# AudioMega_DIL-1206_TOP.net
KiCad netlist of a schematic drawn in EAGLE
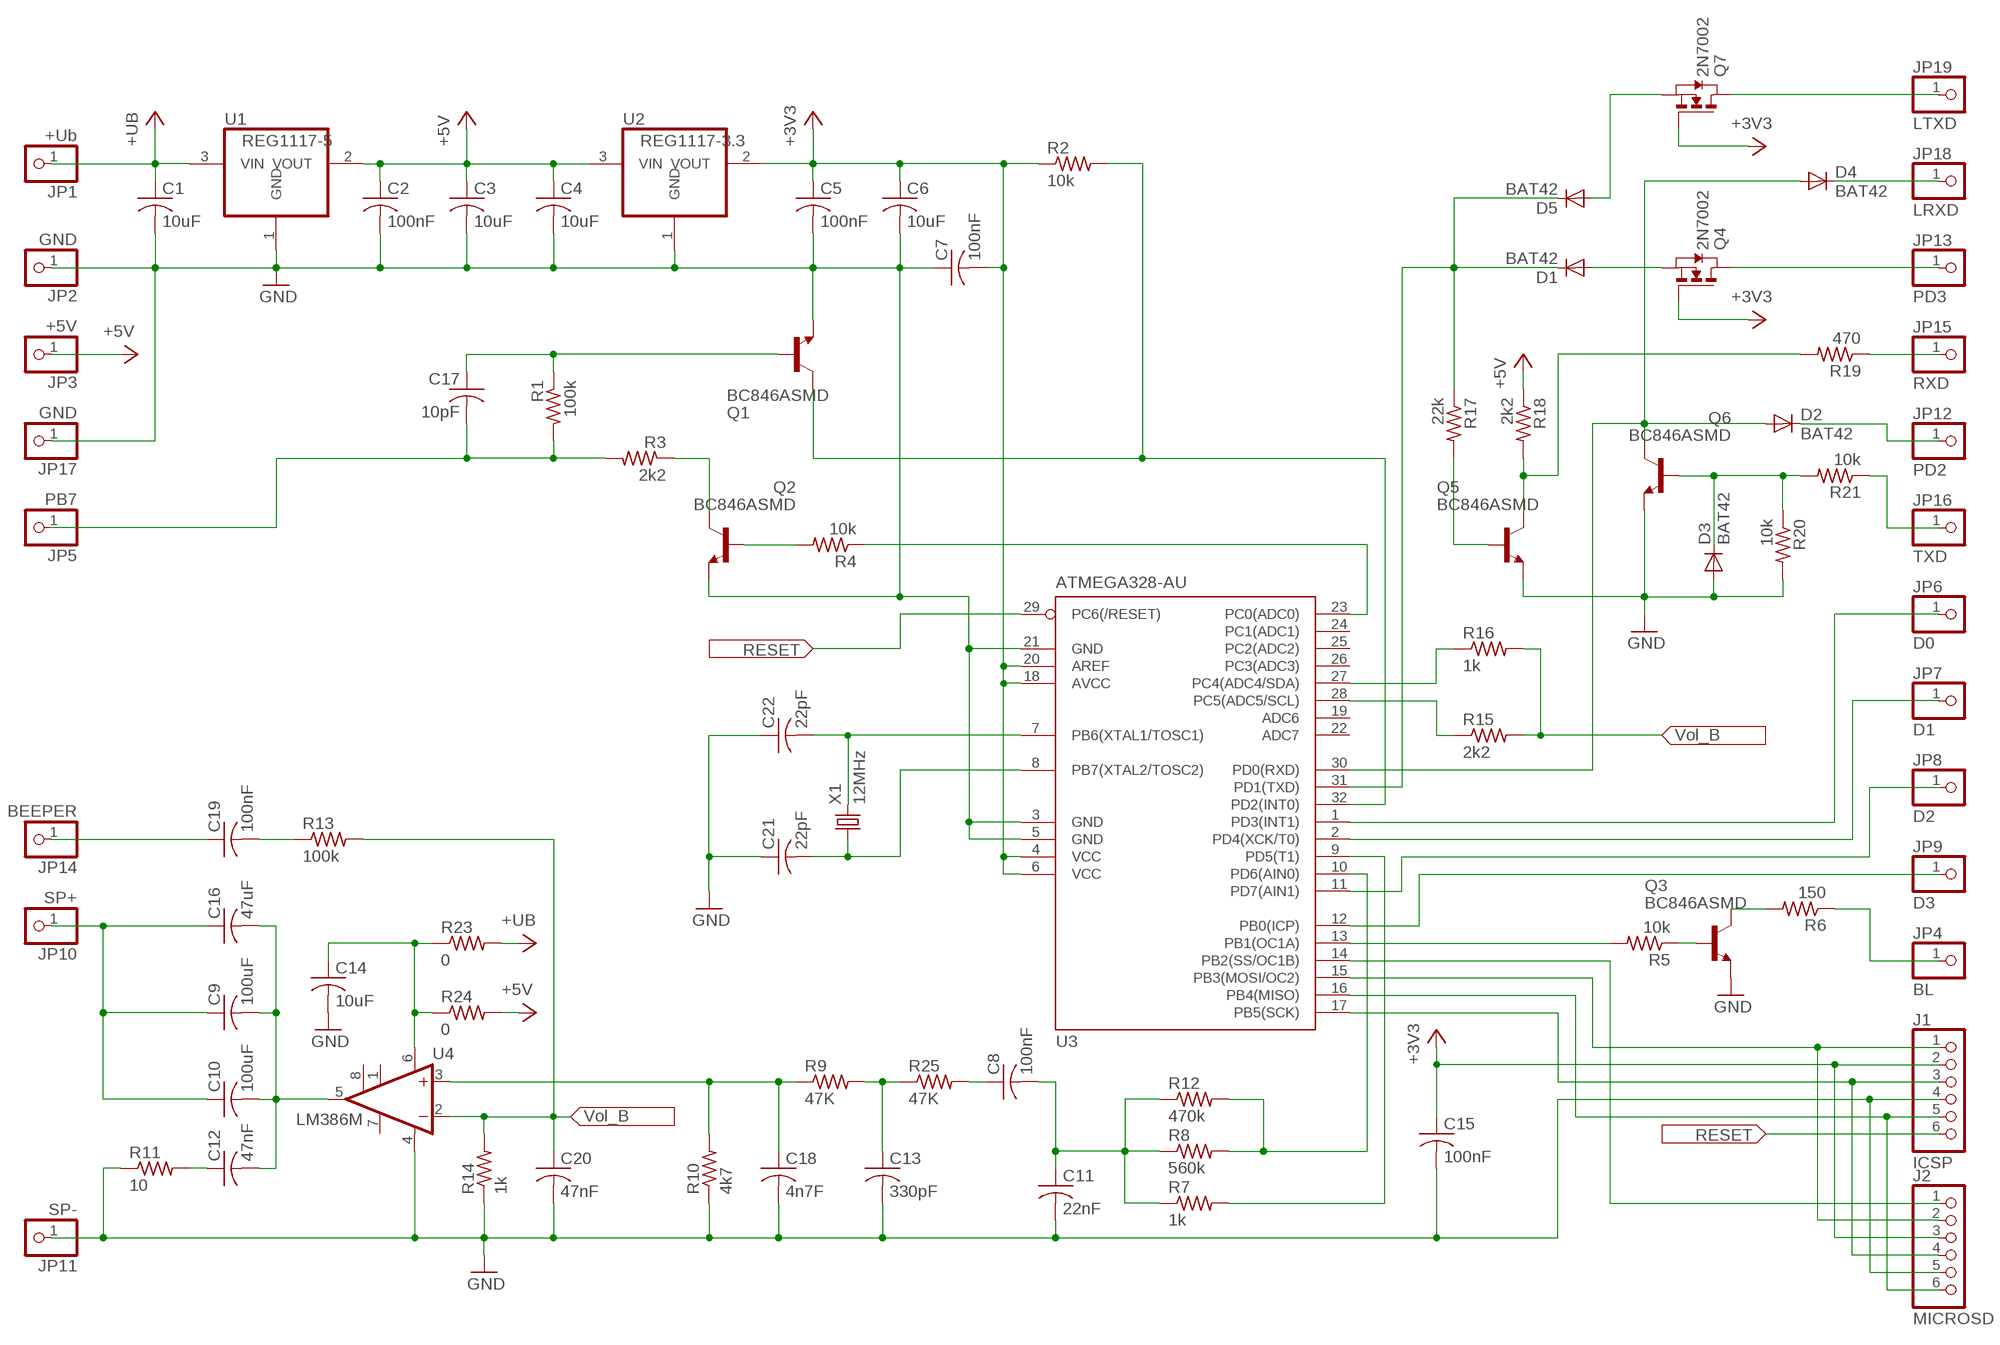
[diagram p0: schematic, sheet 1]

(export (version "E")
  (design (tool "Eeschema 10.0.6"))
  (components
    (comp (ref "C1")
      (value "10uF")
      (footprint "eagle-import:C1206")
      (libsource (lib "eagle-import") (part "C-USC1206"))
    )
    (comp (ref "C2")
      (value "100nF")
      (footprint "eagle-import:C1206")
      (libsource (lib "eagle-import") (part "C-USC1206"))
    )
    (comp (ref "C3")
      (value "10uF")
      (footprint "eagle-import:C1206")
      (libsource (lib "eagle-import") (part "C-USC1206"))
    )
    (comp (ref "C4")
      (value "10uF")
      (footprint "eagle-import:C1206")
      (libsource (lib "eagle-import") (part "C-USC1206"))
    )
    (comp (ref "C5")
      (value "100nF")
      (footprint "eagle-import:C1206")
      (libsource (lib "eagle-import") (part "C-USC1206"))
    )
    (comp (ref "C6")
      (value "10uF")
      (footprint "eagle-import:C1206")
      (libsource (lib "eagle-import") (part "C-USC1206"))
    )
    (comp (ref "C7")
      (value "100nF")
      (footprint "eagle-import:C1206")
      (libsource (lib "eagle-import") (part "C-USC1206"))
    )
    (comp (ref "C8")
      (value "100nF")
      (footprint "eagle-import:C1206")
      (libsource (lib "eagle-import") (part "C-USC1206"))
    )
    (comp (ref "C9")
      (value "100uF")
      (footprint "eagle-import:C1206")
      (libsource (lib "eagle-import") (part "C-USC1206"))
    )
    (comp (ref "C10")
      (value "100uF")
      (footprint "eagle-import:C1206")
      (libsource (lib "eagle-import") (part "C-USC1206"))
    )
    (comp (ref "C11")
      (value "22nF")
      (footprint "eagle-import:C1206")
      (libsource (lib "eagle-import") (part "C-USC1206"))
    )
    (comp (ref "C12")
      (value "47nF")
      (footprint "eagle-import:C1206")
      (libsource (lib "eagle-import") (part "C-USC1206"))
    )
    (comp (ref "C13")
      (value "330pF")
      (footprint "eagle-import:C1206")
      (libsource (lib "eagle-import") (part "C-USC1206"))
    )
    (comp (ref "C14")
      (value "10uF")
      (footprint "eagle-import:C1206")
      (libsource (lib "eagle-import") (part "C-USC1206"))
    )
    (comp (ref "C15")
      (value "100nF")
      (footprint "eagle-import:C1206")
      (libsource (lib "eagle-import") (part "C-USC1206"))
    )
    (comp (ref "C16")
      (value "47uF")
      (footprint "eagle-import:C1206")
      (libsource (lib "eagle-import") (part "C-USC1206"))
    )
    (comp (ref "C17")
      (value "10pF")
      (footprint "eagle-import:C1206")
      (libsource (lib "eagle-import") (part "C-USC1206"))
    )
    (comp (ref "C18")
      (value "4n7F")
      (footprint "eagle-import:C1206")
      (libsource (lib "eagle-import") (part "C-USC1206"))
    )
    (comp (ref "C19")
      (value "100nF")
      (footprint "eagle-import:C1206")
      (libsource (lib "eagle-import") (part "C-USC1206"))
    )
    (comp (ref "C20")
      (value "47nF")
      (footprint "eagle-import:C1206")
      (libsource (lib "eagle-import") (part "C-USC1206"))
    )
    (comp (ref "C21")
      (value "22pF")
      (footprint "eagle-import:C1206")
      (libsource (lib "eagle-import") (part "C-USC1206"))
    )
    (comp (ref "C22")
      (value "22pF")
      (footprint "eagle-import:C1206")
      (libsource (lib "eagle-import") (part "C-USC1206"))
    )
    (comp (ref "D1")
      (value "BAT42")
      (footprint "eagle-import:SOD123")
      (libsource (lib "eagle-import") (part "DIODE-SOD123"))
    )
    (comp (ref "D2")
      (value "BAT42")
      (footprint "eagle-import:SOD123")
      (libsource (lib "eagle-import") (part "DIODE-SOD123"))
    )
    (comp (ref "D3")
      (value "BAT42")
      (footprint "eagle-import:SOD123")
      (libsource (lib "eagle-import") (part "DIODE-SOD123"))
    )
    (comp (ref "D4")
      (value "BAT42")
      (footprint "eagle-import:SOD123")
      (libsource (lib "eagle-import") (part "DIODE-SOD123"))
    )
    (comp (ref "D5")
      (value "BAT42")
      (footprint "eagle-import:SOD123")
      (libsource (lib "eagle-import") (part "DIODE-SOD123"))
    )
    (comp (ref "J1")
      (value "ICSP")
      (footprint "eagle-import:1X06")
      (libsource (lib "eagle-import") (part "PINHD-1X6"))
    )
    (comp (ref "J2")
      (value "MICROSD")
      (footprint "eagle-import:1X06")
      (libsource (lib "eagle-import") (part "PINHD-1X6"))
    )
    (comp (ref "JP1")
      (value "+Ub")
      (footprint "eagle-import:1X01")
      (libsource (lib "eagle-import") (part "PINHD-1X1"))
    )
    (comp (ref "JP2")
      (value "GND")
      (footprint "eagle-import:1X01")
      (libsource (lib "eagle-import") (part "PINHD-1X1"))
    )
    (comp (ref "JP3")
      (value "+5V")
      (footprint "eagle-import:1X01")
      (libsource (lib "eagle-import") (part "PINHD-1X1"))
    )
    (comp (ref "JP4")
      (value "BL")
      (footprint "eagle-import:1X01")
      (libsource (lib "eagle-import") (part "PINHD-1X1"))
    )
    (comp (ref "JP5")
      (value "PB7")
      (footprint "eagle-import:1X01")
      (libsource (lib "eagle-import") (part "PINHD-1X1"))
    )
    (comp (ref "JP6")
      (value "D0")
      (footprint "eagle-import:1X01")
      (libsource (lib "eagle-import") (part "PINHD-1X1"))
    )
    (comp (ref "JP7")
      (value "D1")
      (footprint "eagle-import:1X01")
      (libsource (lib "eagle-import") (part "PINHD-1X1"))
    )
    (comp (ref "JP8")
      (value "D2")
      (footprint "eagle-import:1X01")
      (libsource (lib "eagle-import") (part "PINHD-1X1"))
    )
    (comp (ref "JP9")
      (value "D3")
      (footprint "eagle-import:1X01")
      (libsource (lib "eagle-import") (part "PINHD-1X1"))
    )
    (comp (ref "JP10")
      (value "SP+")
      (footprint "eagle-import:1X01")
      (libsource (lib "eagle-import") (part "PINHD-1X1"))
    )
    (comp (ref "JP11")
      (value "SP-")
      (footprint "eagle-import:1X01")
      (libsource (lib "eagle-import") (part "PINHD-1X1"))
    )
    (comp (ref "JP12")
      (value "PD2")
      (footprint "eagle-import:1X01")
      (libsource (lib "eagle-import") (part "PINHD-1X1"))
    )
    (comp (ref "JP13")
      (value "PD3")
      (footprint "eagle-import:1X01")
      (libsource (lib "eagle-import") (part "PINHD-1X1"))
    )
    (comp (ref "JP14")
      (value "BEEPER")
      (footprint "eagle-import:1X01")
      (libsource (lib "eagle-import") (part "PINHD-1X1"))
    )
    (comp (ref "JP15")
      (value "RXD")
      (footprint "eagle-import:1X01")
      (libsource (lib "eagle-import") (part "PINHD-1X1"))
    )
    (comp (ref "JP16")
      (value "TXD")
      (footprint "eagle-import:1X01")
      (libsource (lib "eagle-import") (part "PINHD-1X1"))
    )
    (comp (ref "JP17")
      (value "GND")
      (footprint "eagle-import:1X01")
      (libsource (lib "eagle-import") (part "PINHD-1X1"))
    )
    (comp (ref "JP18")
      (value "LRXD")
      (footprint "eagle-import:1X01")
      (libsource (lib "eagle-import") (part "PINHD-1X1"))
    )
    (comp (ref "JP19")
      (value "LTXD")
      (footprint "eagle-import:1X01")
      (libsource (lib "eagle-import") (part "PINHD-1X1"))
    )
    (comp (ref "Q1")
      (value "BC846ASMD")
      (footprint "eagle-import:SOT23")
      (libsource (lib "eagle-import") (part "BC846SMDA"))
    )
    (comp (ref "Q2")
      (value "BC846ASMD")
      (footprint "eagle-import:SOT23")
      (libsource (lib "eagle-import") (part "BC846SMDA"))
    )
    (comp (ref "Q3")
      (value "BC846ASMD")
      (footprint "eagle-import:SOT23")
      (libsource (lib "eagle-import") (part "BC846SMDA"))
    )
    (comp (ref "Q4")
      (value "2N7002")
      (footprint "eagle-import:SOT-23")
      (libsource (lib "eagle-import") (part "NMOSSOT23"))
    )
    (comp (ref "Q5")
      (value "BC846ASMD")
      (footprint "eagle-import:SOT23")
      (libsource (lib "eagle-import") (part "BC846SMDA"))
    )
    (comp (ref "Q6")
      (value "BC846ASMD")
      (footprint "eagle-import:SOT23")
      (libsource (lib "eagle-import") (part "BC846SMDA"))
    )
    (comp (ref "Q7")
      (value "2N7002")
      (footprint "eagle-import:SOT-23")
      (fields (field (name "OC_FARNELL") "unknown") (field (name "OC_NEWARK") "unknown"))
      (libsource (lib "eagle-import") (part "NMOSSOT23"))
    )
    (comp (ref "R1")
      (value "100k")
      (footprint "eagle-import:R1206")
      (libsource (lib "eagle-import") (part "resistor_R-US_R1206"))
    )
    (comp (ref "R2")
      (value "10k")
      (footprint "eagle-import:R1206")
      (libsource (lib "eagle-import") (part "resistor_R-US_R1206"))
    )
    (comp (ref "R3")
      (value "2k2")
      (footprint "eagle-import:R1206")
      (libsource (lib "eagle-import") (part "resistor_R-US_R1206"))
    )
    (comp (ref "R4")
      (value "10k")
      (footprint "eagle-import:R1206")
      (libsource (lib "eagle-import") (part "resistor_R-US_R1206"))
    )
    (comp (ref "R5")
      (value "10k")
      (footprint "eagle-import:R1206")
      (libsource (lib "eagle-import") (part "resistor_R-US_R1206"))
    )
    (comp (ref "R6")
      (value "150")
      (footprint "eagle-import:R1206")
      (libsource (lib "eagle-import") (part "resistor_R-US_R1206"))
    )
    (comp (ref "R7")
      (value "1k")
      (footprint "eagle-import:R1206")
      (libsource (lib "eagle-import") (part "resistor_R-US_R1206"))
    )
    (comp (ref "R8")
      (value "560k")
      (footprint "eagle-import:R1206")
      (libsource (lib "eagle-import") (part "resistor_R-US_R1206"))
    )
    (comp (ref "R9")
      (value "47K")
      (footprint "eagle-import:R1206")
      (libsource (lib "eagle-import") (part "resistor_R-US_R1206"))
    )
    (comp (ref "R10")
      (value "4k7")
      (footprint "eagle-import:R1206")
      (libsource (lib "eagle-import") (part "resistor_R-US_R1206"))
    )
    (comp (ref "R11")
      (value "10")
      (footprint "eagle-import:R1206")
      (libsource (lib "eagle-import") (part "resistor_R-US_R1206"))
    )
    (comp (ref "R12")
      (value "470k")
      (footprint "eagle-import:R1206")
      (libsource (lib "eagle-import") (part "resistor_R-US_R1206"))
    )
    (comp (ref "R13")
      (value "100k")
      (footprint "eagle-import:R1206")
      (libsource (lib "eagle-import") (part "resistor_R-US_R1206"))
    )
    (comp (ref "R14")
      (value "1k")
      (footprint "eagle-import:R1206")
      (libsource (lib "eagle-import") (part "resistor_R-US_R1206"))
    )
    (comp (ref "R15")
      (value "2k2")
      (footprint "eagle-import:R1206")
      (libsource (lib "eagle-import") (part "resistor_R-US_R1206"))
    )
    (comp (ref "R16")
      (value "1k")
      (footprint "eagle-import:R1206")
      (libsource (lib "eagle-import") (part "resistor_R-US_R1206"))
    )
    (comp (ref "R17")
      (value "22k")
      (footprint "eagle-import:R1206")
      (libsource (lib "eagle-import") (part "resistor_R-US_R1206"))
    )
    (comp (ref "R18")
      (value "2k2")
      (footprint "eagle-import:R1206")
      (libsource (lib "eagle-import") (part "resistor_R-US_R1206"))
    )
    (comp (ref "R19")
      (value "470")
      (footprint "eagle-import:R1206")
      (libsource (lib "eagle-import") (part "resistor_R-US_R1206"))
    )
    (comp (ref "R20")
      (value "10k")
      (footprint "eagle-import:R1206")
      (libsource (lib "eagle-import") (part "resistor_R-US_R1206"))
    )
    (comp (ref "R21")
      (value "10k")
      (footprint "eagle-import:R1206")
      (libsource (lib "eagle-import") (part "resistor_R-US_R1206"))
    )
    (comp (ref "R23")
      (value "0")
      (footprint "eagle-import:R1206")
      (libsource (lib "eagle-import") (part "R-US_R1206"))
    )
    (comp (ref "R24")
      (value "0")
      (footprint "eagle-import:R1206")
      (libsource (lib "eagle-import") (part "R-US_R1206"))
    )
    (comp (ref "R25")
      (value "47K")
      (footprint "eagle-import:R1206")
      (libsource (lib "eagle-import") (part "resistor_R-US_R1206"))
    )
    (comp (ref "U1")
      (value "REG1117-5")
      (footprint "eagle-import:SOT223")
      (fields (field (name "MPN") "REG1117"))
      (libsource (lib "eagle-import") (part "REG1117"))
    )
    (comp (ref "U2")
      (value "REG1117-3.3")
      (footprint "eagle-import:SOT223")
      (fields (field (name "MPN") "REG1117"))
      (libsource (lib "eagle-import") (part "REG1117"))
    )
    (comp (ref "U3")
      (value "ATMEGA328-AU")
      (footprint "eagle-import:TQFP32-08")
      (fields (field (name "MPN") "ATMEGA8-16AU"))
      (libsource (lib "eagle-import") (part "MEGA8-AI"))
    )
    (comp (ref "U4")
      (value "LM386M")
      (footprint "eagle-import:SO08")
      (libsource (lib "eagle-import") (part "LM386?-M1"))
    )
    (comp (ref "X1")
      (value "12MHz")
      (footprint "eagle-import:HC49US")
      (libsource (lib "eagle-import") (part "CSM-3XHC49/US"))
    )
  )
  (nets
    (net (code "1") (name "+3V3") (class "Default")
      (node (ref "C15") (pin "1") (pinfunction "1_1") (pintype "passive"))
      (node (ref "C5") (pin "1") (pinfunction "1_1") (pintype "passive"))
      (node (ref "C6") (pin "1") (pinfunction "1_1") (pintype "passive"))
      (node (ref "C7") (pin "2") (pinfunction "2_2") (pintype "passive"))
      (node (ref "J1") (pin "2") (pinfunction "2_2") (pintype "passive"))
      (node (ref "J2") (pin "3") (pinfunction "3_3") (pintype "passive"))
      (node (ref "Q4") (pin "3") (pinfunction "G_3") (pintype "passive"))
      (node (ref "Q7") (pin "3") (pinfunction "G_3") (pintype "passive"))
      (node (ref "R2") (pin "1") (pinfunction "1_1") (pintype "passive"))
      (node (ref "U2") (pin "2") (pinfunction "VOUT_2") (pintype "output"))
      (node (ref "U3") (pin "18") (pinfunction "AVCC_18") (pintype "power_in"))
      (node (ref "U3") (pin "20") (pinfunction "AREF_20") (pintype "passive"))
      (node (ref "U3") (pin "4") (pinfunction "VCC_4") (pintype "power_in"))
      (node (ref "U3") (pin "6") (pinfunction "VCC_6") (pintype "power_in"))
    )
    (net (code "2") (name "+5V") (class "Default")
      (node (ref "C2") (pin "1") (pinfunction "1_1") (pintype "passive"))
      (node (ref "C3") (pin "1") (pinfunction "1_1") (pintype "passive"))
      (node (ref "C4") (pin "1") (pinfunction "1_1") (pintype "passive"))
      (node (ref "JP3") (pin "1") (pinfunction "1_1") (pintype "passive"))
      (node (ref "R18") (pin "1") (pinfunction "1_1") (pintype "passive"))
      (node (ref "R24") (pin "2") (pinfunction "2_2") (pintype "passive"))
      (node (ref "U1") (pin "2") (pinfunction "VOUT_2") (pintype "output"))
      (node (ref "U2") (pin "3") (pinfunction "VIN_3") (pintype "input"))
    )
    (net (code "3") (name "+UB") (class "Default")
      (node (ref "C1") (pin "1") (pinfunction "1_1") (pintype "passive"))
      (node (ref "JP1") (pin "1") (pinfunction "1_1") (pintype "passive"))
      (node (ref "R23") (pin "2") (pinfunction "2_2") (pintype "passive"))
      (node (ref "U1") (pin "3") (pinfunction "VIN_3") (pintype "input"))
    )
    (net (code "4") (name "/RESET") (class "Default")
      (node (ref "J1") (pin "6") (pinfunction "6_6") (pintype "passive"))
      (node (ref "U3") (pin "29") (pinfunction "PC6(/RESET)_29") (pintype "bidirectional"))
    )
    (net (code "5") (name "/VOL_B") (class "Default")
      (node (ref "C20") (pin "1") (pinfunction "1_1") (pintype "passive"))
      (node (ref "R13") (pin "2") (pinfunction "2_2") (pintype "passive"))
      (node (ref "R14") (pin "2") (pinfunction "2_2") (pintype "passive"))
      (node (ref "R15") (pin "2") (pinfunction "2_2") (pintype "passive"))
      (node (ref "R16") (pin "2") (pinfunction "2_2") (pintype "passive"))
      (node (ref "U4") (pin "2") (pinfunction "-IN_2") (pintype "input"))
    )
    (net (code "6") (name "GND") (class "Default")
      (node (ref "C1") (pin "2") (pinfunction "2_2") (pintype "passive"))
      (node (ref "C11") (pin "2") (pinfunction "2_2") (pintype "passive"))
      (node (ref "C13") (pin "2") (pinfunction "2_2") (pintype "passive"))
      (node (ref "C14") (pin "2") (pinfunction "2_2") (pintype "passive"))
      (node (ref "C15") (pin "2") (pinfunction "2_2") (pintype "passive"))
      (node (ref "C18") (pin "2") (pinfunction "2_2") (pintype "passive"))
      (node (ref "C2") (pin "2") (pinfunction "2_2") (pintype "passive"))
      (node (ref "C20") (pin "2") (pinfunction "2_2") (pintype "passive"))
      (node (ref "C21") (pin "1") (pinfunction "1_1") (pintype "passive"))
      (node (ref "C22") (pin "1") (pinfunction "1_1") (pintype "passive"))
      (node (ref "C3") (pin "2") (pinfunction "2_2") (pintype "passive"))
      (node (ref "C4") (pin "2") (pinfunction "2_2") (pintype "passive"))
      (node (ref "C5") (pin "2") (pinfunction "2_2") (pintype "passive"))
      (node (ref "C6") (pin "2") (pinfunction "2_2") (pintype "passive"))
      (node (ref "C7") (pin "1") (pinfunction "1_1") (pintype "passive"))
      (node (ref "D3") (pin "A") (pinfunction "A_A") (pintype "passive"))
      (node (ref "J1") (pin "4") (pinfunction "4_4") (pintype "passive"))
      (node (ref "J2") (pin "5") (pinfunction "5_5") (pintype "passive"))
      (node (ref "JP11") (pin "1") (pinfunction "1_1") (pintype "passive"))
      (node (ref "JP17") (pin "1") (pinfunction "1_1") (pintype "passive"))
      (node (ref "JP2") (pin "1") (pinfunction "1_1") (pintype "passive"))
      (node (ref "Q1") (pin "2") (pinfunction "E_2") (pintype "passive"))
      (node (ref "Q2") (pin "2") (pinfunction "E_2") (pintype "passive"))
      (node (ref "Q3") (pin "2") (pinfunction "E_2") (pintype "passive"))
      (node (ref "Q5") (pin "2") (pinfunction "E_2") (pintype "passive"))
      (node (ref "Q6") (pin "2") (pinfunction "E_2") (pintype "passive"))
      (node (ref "R10") (pin "1") (pinfunction "1_1") (pintype "passive"))
      (node (ref "R11") (pin "1") (pinfunction "1_1") (pintype "passive"))
      (node (ref "R14") (pin "1") (pinfunction "1_1") (pintype "passive"))
      (node (ref "R20") (pin "2") (pinfunction "2_2") (pintype "passive"))
      (node (ref "U1") (pin "1") (pinfunction "GND_1") (pintype "power_in"))
      (node (ref "U2") (pin "1") (pinfunction "GND_1") (pintype "power_in"))
      (node (ref "U3") (pin "21") (pinfunction "GND_21") (pintype "power_in"))
      (node (ref "U3") (pin "3") (pinfunction "GND_3") (pintype "power_in"))
      (node (ref "U3") (pin "5") (pinfunction "GND_5") (pintype "power_in"))
      (node (ref "U4") (pin "4") (pinfunction "GND_4") (pintype "power_in"))
    )
    (net (code "7") (name "Net-(C8-Pad1)") (class "Default")
      (node (ref "C8") (pin "1") (pinfunction "1_1") (pintype "passive"))
      (node (ref "R25") (pin "2") (pinfunction "2_2") (pintype "passive"))
    )
    (net (code "8") (name "Net-(C10-Pad1)") (class "Default")
      (node (ref "C10") (pin "1") (pinfunction "1_1") (pintype "passive"))
      (node (ref "C16") (pin "1") (pinfunction "1_1") (pintype "passive"))
      (node (ref "C9") (pin "1") (pinfunction "1_1") (pintype "passive"))
      (node (ref "JP10") (pin "1") (pinfunction "1_1") (pintype "passive"))
    )
    (net (code "9") (name "Net-(C11-Pad1)") (class "Default")
      (node (ref "C11") (pin "1") (pinfunction "1_1") (pintype "passive"))
      (node (ref "C8") (pin "2") (pinfunction "2_2") (pintype "passive"))
      (node (ref "R12") (pin "1") (pinfunction "1_1") (pintype "passive"))
      (node (ref "R7") (pin "1") (pinfunction "1_1") (pintype "passive"))
      (node (ref "R8") (pin "1") (pinfunction "1_1") (pintype "passive"))
    )
    (net (code "10") (name "Net-(C12-Pad1)") (class "Default")
      (node (ref "C12") (pin "1") (pinfunction "1_1") (pintype "passive"))
      (node (ref "R11") (pin "2") (pinfunction "2_2") (pintype "passive"))
    )
    (net (code "11") (name "Net-(C13-Pad1)") (class "Default")
      (node (ref "C13") (pin "1") (pinfunction "1_1") (pintype "passive"))
      (node (ref "R25") (pin "1") (pinfunction "1_1") (pintype "passive"))
      (node (ref "R9") (pin "2") (pinfunction "2_2") (pintype "passive"))
    )
    (net (code "12") (name "Net-(C17-Pad2)") (class "Default")
      (node (ref "C17") (pin "2") (pinfunction "2_2") (pintype "passive"))
      (node (ref "JP5") (pin "1") (pinfunction "1_1") (pintype "passive"))
      (node (ref "R1") (pin "2") (pinfunction "2_2") (pintype "passive"))
      (node (ref "R3") (pin "2") (pinfunction "2_2") (pintype "passive"))
    )
    (net (code "13") (name "Net-(C19-Pad1)") (class "Default")
      (node (ref "C19") (pin "1") (pinfunction "1_1") (pintype "passive"))
      (node (ref "JP14") (pin "1") (pinfunction "1_1") (pintype "passive"))
    )
    (net (code "14") (name "Net-(C19-Pad2)") (class "Default")
      (node (ref "C19") (pin "2") (pinfunction "2_2") (pintype "passive"))
      (node (ref "R13") (pin "1") (pinfunction "1_1") (pintype "passive"))
    )
    (net (code "15") (name "Net-(D2-PadC)") (class "Default")
      (node (ref "D2") (pin "C") (pinfunction "C_C") (pintype "passive"))
      (node (ref "JP12") (pin "1") (pinfunction "1_1") (pintype "passive"))
    )
    (net (code "16") (name "Net-(D4-PadC)") (class "Default")
      (node (ref "D4") (pin "C") (pinfunction "C_C") (pintype "passive"))
      (node (ref "JP18") (pin "1") (pinfunction "1_1") (pintype "passive"))
    )
    (net (code "17") (name "Net-(JP4-Pad1)") (class "Default")
      (node (ref "JP4") (pin "1") (pinfunction "1_1") (pintype "passive"))
      (node (ref "R6") (pin "1") (pinfunction "1_1") (pintype "passive"))
    )
    (net (code "18") (name "Net-(JP15-Pad1)") (class "Default")
      (node (ref "JP15") (pin "1") (pinfunction "1_1") (pintype "passive"))
      (node (ref "R19") (pin "1") (pinfunction "1_1") (pintype "passive"))
    )
    (net (code "19") (name "Net-(JP16-Pad1)") (class "Default")
      (node (ref "JP16") (pin "1") (pinfunction "1_1") (pintype "passive"))
      (node (ref "R21") (pin "1") (pinfunction "1_1") (pintype "passive"))
    )
    (net (code "20") (name "Net-(Q1-B)") (class "Default")
      (node (ref "C17") (pin "1") (pinfunction "1_1") (pintype "passive"))
      (node (ref "Q1") (pin "1") (pinfunction "B_1") (pintype "passive"))
      (node (ref "R1") (pin "1") (pinfunction "1_1") (pintype "passive"))
    )
    (net (code "21") (name "Net-(Q1-C)") (class "Default")
      (node (ref "Q1") (pin "3") (pinfunction "C_3") (pintype "passive"))
      (node (ref "R2") (pin "2") (pinfunction "2_2") (pintype "passive"))
      (node (ref "U3") (pin "32") (pinfunction "PD2(INT0)_32") (pintype "bidirectional"))
    )
    (net (code "22") (name "Net-(Q2-B)") (class "Default")
      (node (ref "Q2") (pin "1") (pinfunction "B_1") (pintype "passive"))
      (node (ref "R4") (pin "2") (pinfunction "2_2") (pintype "passive"))
    )
    (net (code "23") (name "Net-(Q2-C)") (class "Default")
      (node (ref "Q2") (pin "3") (pinfunction "C_3") (pintype "passive"))
      (node (ref "R3") (pin "1") (pinfunction "1_1") (pintype "passive"))
    )
    (net (code "24") (name "Net-(Q3-B)") (class "Default")
      (node (ref "Q3") (pin "1") (pinfunction "B_1") (pintype "passive"))
      (node (ref "R5") (pin "1") (pinfunction "1_1") (pintype "passive"))
    )
    (net (code "25") (name "Net-(Q3-C)") (class "Default")
      (node (ref "Q3") (pin "3") (pinfunction "C_3") (pintype "passive"))
      (node (ref "R6") (pin "2") (pinfunction "2_2") (pintype "passive"))
    )
    (net (code "26") (name "Net-(Q4-D)") (class "Default")
      (node (ref "JP13") (pin "1") (pinfunction "1_1") (pintype "passive"))
      (node (ref "Q4") (pin "1") (pinfunction "D_1") (pintype "passive"))
    )
    (net (code "27") (name "Net-(Q4-S)") (class "Default")
      (node (ref "D1") (pin "A") (pinfunction "A_A") (pintype "passive"))
      (node (ref "Q4") (pin "2") (pinfunction "S_2") (pintype "passive"))
    )
    (net (code "28") (name "Net-(Q5-B)") (class "Default")
      (node (ref "Q5") (pin "1") (pinfunction "B_1") (pintype "passive"))
      (node (ref "R17") (pin "2") (pinfunction "2_2") (pintype "passive"))
    )
    (net (code "29") (name "Net-(Q5-C)") (class "Default")
      (node (ref "Q5") (pin "3") (pinfunction "C_3") (pintype "passive"))
      (node (ref "R18") (pin "2") (pinfunction "2_2") (pintype "passive"))
      (node (ref "R19") (pin "2") (pinfunction "2_2") (pintype "passive"))
    )
    (net (code "30") (name "Net-(Q6-B)") (class "Default")
      (node (ref "D3") (pin "C") (pinfunction "C_C") (pintype "passive"))
      (node (ref "Q6") (pin "1") (pinfunction "B_1") (pintype "passive"))
      (node (ref "R20") (pin "1") (pinfunction "1_1") (pintype "passive"))
      (node (ref "R21") (pin "2") (pinfunction "2_2") (pintype "passive"))
    )
    (net (code "31") (name "Net-(Q6-C)") (class "Default")
      (node (ref "D2") (pin "A") (pinfunction "A_A") (pintype "passive"))
      (node (ref "D4") (pin "A") (pinfunction "A_A") (pintype "passive"))
      (node (ref "Q6") (pin "3") (pinfunction "C_3") (pintype "passive"))
      (node (ref "U3") (pin "30") (pinfunction "PD0(RXD)_30") (pintype "bidirectional"))
    )
    (net (code "32") (name "Net-(Q7-D)") (class "Default")
      (node (ref "JP19") (pin "1") (pinfunction "1_1") (pintype "passive"))
      (node (ref "Q7") (pin "1") (pinfunction "D_1") (pintype "passive"))
    )
    (net (code "33") (name "Net-(Q7-S)") (class "Default")
      (node (ref "D5") (pin "A") (pinfunction "A_A") (pintype "passive"))
      (node (ref "Q7") (pin "2") (pinfunction "S_2") (pintype "passive"))
    )
    (net (code "34") (name "Net-(U3-PB0(ICP))") (class "Default")
      (node (ref "JP9") (pin "1") (pinfunction "1_1") (pintype "passive"))
      (node (ref "U3") (pin "12") (pinfunction "PB0(ICP)_12") (pintype "bidirectional"))
    )
    (net (code "35") (name "Net-(U3-PB1(OC1A))") (class "Default")
      (node (ref "R5") (pin "2") (pinfunction "2_2") (pintype "passive"))
      (node (ref "U3") (pin "13") (pinfunction "PB1(OC1A)_13") (pintype "bidirectional"))
    )
    (net (code "36") (name "Net-(U3-PB2(SS{slash}OC1B))") (class "Default")
      (node (ref "J2") (pin "1") (pinfunction "1_1") (pintype "passive"))
      (node (ref "U3") (pin "14") (pinfunction "PB2(SS/OC1B)_14") (pintype "bidirectional"))
    )
    (net (code "37") (name "Net-(U3-PB3(MOSI{slash}OC2))") (class "Default")
      (node (ref "J1") (pin "1") (pinfunction "1_1") (pintype "passive"))
      (node (ref "J2") (pin "2") (pinfunction "2_2") (pintype "passive"))
      (node (ref "U3") (pin "15") (pinfunction "PB3(MOSI/OC2)_15") (pintype "bidirectional"))
    )
    (net (code "38") (name "Net-(U3-PB4(MISO))") (class "Default")
      (node (ref "J1") (pin "5") (pinfunction "5_5") (pintype "passive"))
      (node (ref "J2") (pin "6") (pinfunction "6_6") (pintype "passive"))
      (node (ref "U3") (pin "16") (pinfunction "PB4(MISO)_16") (pintype "bidirectional"))
    )
    (net (code "39") (name "Net-(U3-PB5(SCK))") (class "Default")
      (node (ref "J1") (pin "3") (pinfunction "3_3") (pintype "passive"))
      (node (ref "J2") (pin "4") (pinfunction "4_4") (pintype "passive"))
      (node (ref "U3") (pin "17") (pinfunction "PB5(SCK)_17") (pintype "bidirectional"))
    )
    (net (code "40") (name "Net-(U3-PB6(XTAL1{slash}TOSC1))") (class "Default")
      (node (ref "C22") (pin "2") (pinfunction "2_2") (pintype "passive"))
      (node (ref "U3") (pin "7") (pinfunction "PB6(XTAL1/TOSC1)_7") (pintype "bidirectional"))
      (node (ref "X1") (pin "2") (pinfunction "2_2") (pintype "passive"))
    )
    (net (code "41") (name "Net-(U3-PB7(XTAL2{slash}TOSC2))") (class "Default")
      (node (ref "C21") (pin "2") (pinfunction "2_2") (pintype "passive"))
      (node (ref "U3") (pin "8") (pinfunction "PB7(XTAL2/TOSC2)_8") (pintype "bidirectional"))
      (node (ref "X1") (pin "1") (pinfunction "1_1") (pintype "passive"))
    )
    (net (code "42") (name "Net-(U3-PC0(ADC0))") (class "Default")
      (node (ref "R4") (pin "1") (pinfunction "1_1") (pintype "passive"))
      (node (ref "U3") (pin "23") (pinfunction "PC0(ADC0)_23") (pintype "bidirectional"))
    )
    (net (code "43") (name "Net-(U3-PC4(ADC4{slash}SDA))") (class "Default")
      (node (ref "R16") (pin "1") (pinfunction "1_1") (pintype "passive"))
      (node (ref "U3") (pin "27") (pinfunction "PC4(ADC4/SDA)_27") (pintype "bidirectional"))
    )
    (net (code "44") (name "Net-(U3-PC5(ADC5{slash}SCL))") (class "Default")
      (node (ref "R15") (pin "1") (pinfunction "1_1") (pintype "passive"))
      (node (ref "U3") (pin "28") (pinfunction "PC5(ADC5/SCL)_28") (pintype "bidirectional"))
    )
    (net (code "45") (name "Net-(U3-PD1(TXD))") (class "Default")
      (node (ref "D1") (pin "C") (pinfunction "C_C") (pintype "passive"))
      (node (ref "D5") (pin "C") (pinfunction "C_C") (pintype "passive"))
      (node (ref "R17") (pin "1") (pinfunction "1_1") (pintype "passive"))
      (node (ref "U3") (pin "31") (pinfunction "PD1(TXD)_31") (pintype "bidirectional"))
    )
    (net (code "46") (name "Net-(U3-PD3(INT1))") (class "Default")
      (node (ref "JP6") (pin "1") (pinfunction "1_1") (pintype "passive"))
      (node (ref "U3") (pin "1") (pinfunction "PD3(INT1)_1") (pintype "bidirectional"))
    )
    (net (code "47") (name "Net-(U3-PD4(XCK{slash}T0))") (class "Default")
      (node (ref "JP7") (pin "1") (pinfunction "1_1") (pintype "passive"))
      (node (ref "U3") (pin "2") (pinfunction "PD4(XCK/T0)_2") (pintype "bidirectional"))
    )
    (net (code "48") (name "Net-(U3-PD5(T1))") (class "Default")
      (node (ref "R7") (pin "2") (pinfunction "2_2") (pintype "passive"))
      (node (ref "U3") (pin "9") (pinfunction "PD5(T1)_9") (pintype "bidirectional"))
    )
    (net (code "49") (name "Net-(U3-PD6(AIN0))") (class "Default")
      (node (ref "R12") (pin "2") (pinfunction "2_2") (pintype "passive"))
      (node (ref "R8") (pin "2") (pinfunction "2_2") (pintype "passive"))
      (node (ref "U3") (pin "10") (pinfunction "PD6(AIN0)_10") (pintype "bidirectional"))
    )
    (net (code "50") (name "Net-(U3-PD7(AIN1))") (class "Default")
      (node (ref "JP8") (pin "1") (pinfunction "1_1") (pintype "passive"))
      (node (ref "U3") (pin "11") (pinfunction "PD7(AIN1)_11") (pintype "bidirectional"))
    )
    (net (code "51") (name "Net-(U4-+IN)") (class "Default")
      (node (ref "C18") (pin "1") (pinfunction "1_1") (pintype "passive"))
      (node (ref "R10") (pin "2") (pinfunction "2_2") (pintype "passive"))
      (node (ref "R9") (pin "1") (pinfunction "1_1") (pintype "passive"))
      (node (ref "U4") (pin "3") (pinfunction "+IN_3") (pintype "input"))
    )
    (net (code "52") (name "Net-(U4-OUT)") (class "Default")
      (node (ref "C10") (pin "2") (pinfunction "2_2") (pintype "passive"))
      (node (ref "C12") (pin "2") (pinfunction "2_2") (pintype "passive"))
      (node (ref "C16") (pin "2") (pinfunction "2_2") (pintype "passive"))
      (node (ref "C9") (pin "2") (pinfunction "2_2") (pintype "passive"))
      (node (ref "U4") (pin "5") (pinfunction "OUT_5") (pintype "output"))
    )
    (net (code "53") (name "Net-(U4-VS)") (class "Default")
      (node (ref "C14") (pin "1") (pinfunction "1_1") (pintype "passive"))
      (node (ref "R23") (pin "1") (pinfunction "1_1") (pintype "passive"))
      (node (ref "R24") (pin "1") (pinfunction "1_1") (pintype "passive"))
      (node (ref "U4") (pin "6") (pinfunction "VS_6") (pintype "power_in"))
    )
    (net (code "54") (name "unconnected-(U3-ADC6-Pad19)") (class "Default")
      (node (ref "U3") (pin "19") (pinfunction "ADC6_19") (pintype "bidirectional"))
    )
    (net (code "55") (name "unconnected-(U3-ADC7-Pad22)") (class "Default")
      (node (ref "U3") (pin "22") (pinfunction "ADC7_22") (pintype "bidirectional"))
    )
    (net (code "56") (name "unconnected-(U3-PC1(ADC1)-Pad24)") (class "Default")
      (node (ref "U3") (pin "24") (pinfunction "PC1(ADC1)_24") (pintype "bidirectional"))
    )
    (net (code "57") (name "unconnected-(U3-PC2(ADC2)-Pad25)") (class "Default")
      (node (ref "U3") (pin "25") (pinfunction "PC2(ADC2)_25") (pintype "bidirectional"))
    )
    (net (code "58") (name "unconnected-(U3-PC3(ADC3)-Pad26)") (class "Default")
      (node (ref "U3") (pin "26") (pinfunction "PC3(ADC3)_26") (pintype "bidirectional"))
    )
    (net (code "59") (name "unconnected-(U4-BYPASS-Pad7)") (class "Default")
      (node (ref "U4") (pin "7") (pinfunction "BYPASS_7") (pintype "passive"))
    )
    (net (code "60") (name "unconnected-(U4-GAIN-Pad1)") (class "Default")
      (node (ref "U4") (pin "1") (pinfunction "GAIN_1") (pintype "passive"))
    )
    (net (code "61") (name "unconnected-(U4-GAIN-Pad8)") (class "Default")
      (node (ref "U4") (pin "8") (pinfunction "GAIN_8") (pintype "passive"))
    )
  )
)
